# Main.net
KiCad netlist of a schematic drawn in Altium Designer
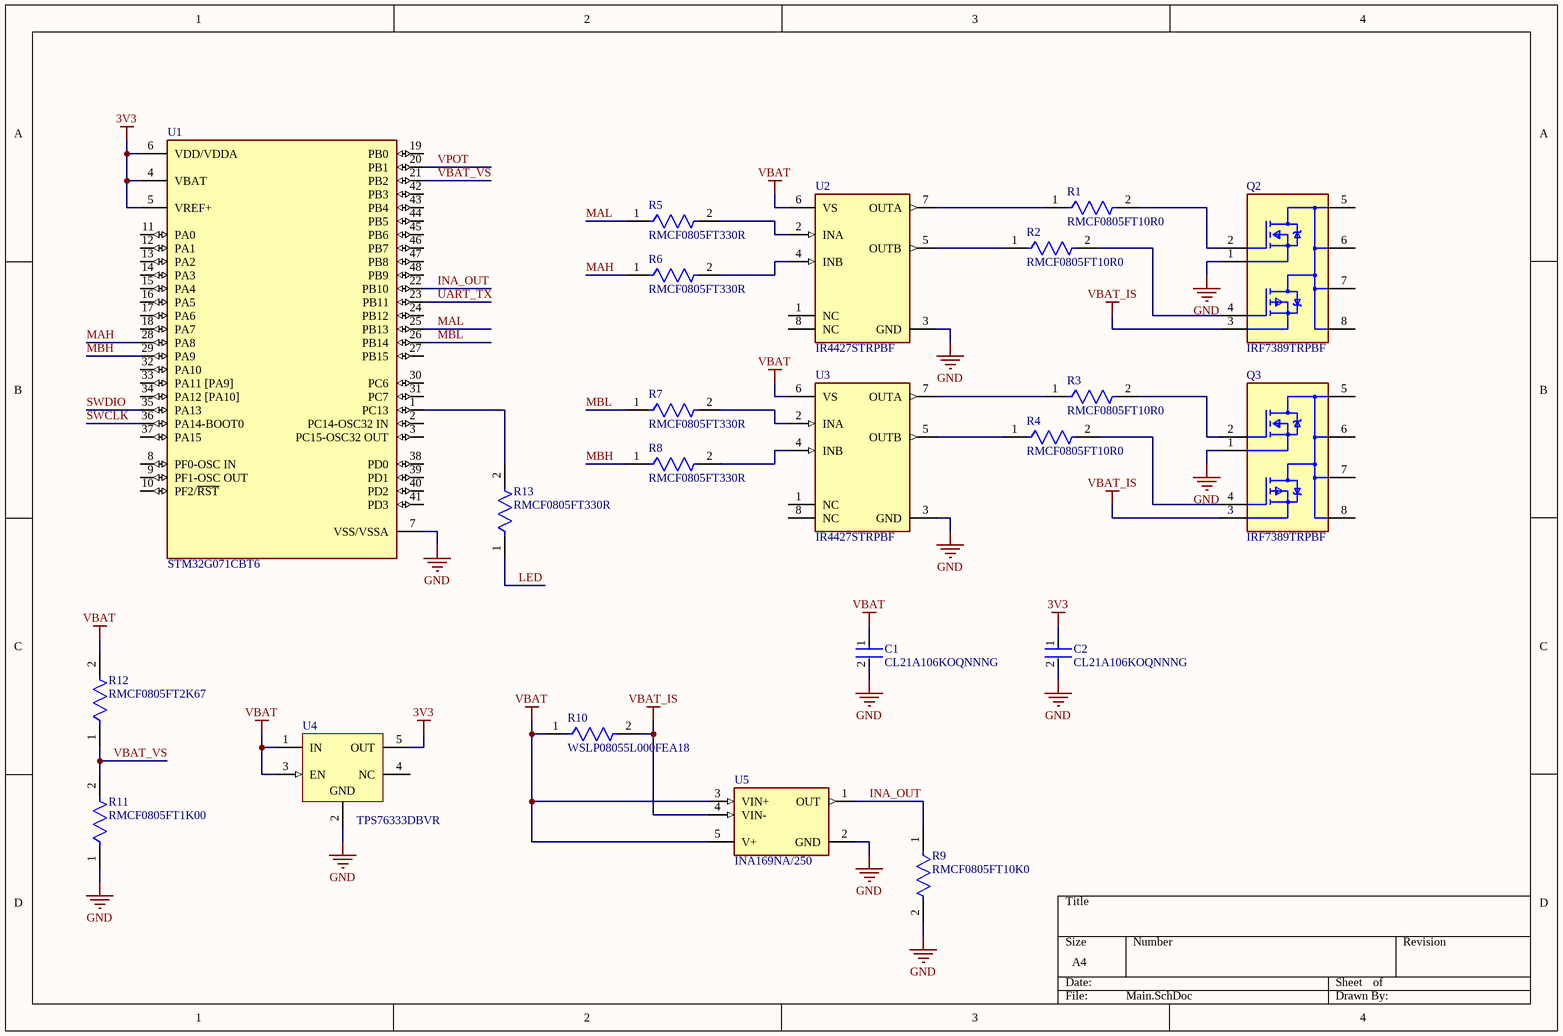
[diagram p0: Main.SchDoc]

(export (version "E")
  (design (tool "Eeschema 10.0.6"))
  (components
    (comp (ref "C1")
      (value "CL21A106KOQNNNG")
      (footprint "FP-CL21-IPC_C")
      (description "CL21 Series 0805 10uF 16V ±10% Tolerance X5R Multilayer Ceramic Chip Capacitor")
      (fields (field (name "TOLERANCE") "10%") (field (name "VOLTAGE") "16V"))
      (libsource (lib "Altium Content Vault") (part "b4654b650e69147ec39a6b967a45e02"))
    )
    (comp (ref "C2")
      (value "CL21A106KOQNNNG")
      (footprint "FP-CL21-IPC_C")
      (description "CL21 Series 0805 10uF 16V ±10% Tolerance X5R Multilayer Ceramic Chip Capacitor")
      (fields (field (name "TOLERANCE") "10%") (field (name "VOLTAGE") "16V"))
      (libsource (lib "Altium Content Vault") (part "b4654b650e69147ec39a6b967a45e02"))
    )
    (comp (ref "Q2")
      (value "IRF7389TRPBF")
      (footprint "FP-PG-DSO-8-MFG")
      (description "MOSFET N/P-CH 30V 8-SOIC")
      (libsource (lib "Altium Content Vault") (part "4824cb7145227b916d674334c6d10b0"))
    )
    (comp (ref "Q3")
      (value "IRF7389TRPBF")
      (footprint "FP-PG-DSO-8-MFG")
      (description "MOSFET N/P-CH 30V 8-SOIC")
      (libsource (lib "Altium Content Vault") (part "4824cb7145227b916d674334c6d10b0"))
    )
    (comp (ref "R1")
      (value "RMCF0805FT10R0")
      (footprint "FP-RMCF0805-IPC_C")
      (description "10Ω ±1% 0.125W 0805 Thick Film Chip Resistor AEC-Q200 compliant")
      (fields (field (name "TOLERANCE") "1%"))
      (libsource (lib "Altium Content Vault") (part "1029c3af85768c4190bb7ad29bc67b5"))
    )
    (comp (ref "R2")
      (value "RMCF0805FT10R0")
      (footprint "FP-RMCF0805-IPC_C")
      (description "10Ω ±1% 0.125W 0805 Thick Film Chip Resistor AEC-Q200 compliant")
      (fields (field (name "TOLERANCE") "1%"))
      (libsource (lib "Altium Content Vault") (part "1029c3af85768c4190bb7ad29bc67b5"))
    )
    (comp (ref "R3")
      (value "RMCF0805FT10R0")
      (footprint "FP-RMCF0805-IPC_C")
      (description "10Ω ±1% 0.125W 0805 Thick Film Chip Resistor AEC-Q200 compliant")
      (fields (field (name "TOLERANCE") "1%"))
      (libsource (lib "Altium Content Vault") (part "1029c3af85768c4190bb7ad29bc67b5"))
    )
    (comp (ref "R4")
      (value "RMCF0805FT10R0")
      (footprint "FP-RMCF0805-IPC_C")
      (description "10Ω ±1% 0.125W 0805 Thick Film Chip Resistor AEC-Q200 compliant")
      (fields (field (name "TOLERANCE") "1%"))
      (libsource (lib "Altium Content Vault") (part "1029c3af85768c4190bb7ad29bc67b5"))
    )
    (comp (ref "R5")
      (value "RMCF0805FT330R")
      (footprint "FP-RMCF0805-IPC_C")
      (description "330Ω ±1% 0.125W 0805 Thick Film Chip Resistor AEC-Q200 compliant")
      (fields (field (name "TOLERANCE") "1%"))
      (libsource (lib "Altium Content Vault") (part "1029c3af85768c4190bb7ad29bc67b5"))
    )
    (comp (ref "R6")
      (value "RMCF0805FT330R")
      (footprint "FP-RMCF0805-IPC_C")
      (description "330Ω ±1% 0.125W 0805 Thick Film Chip Resistor AEC-Q200 compliant")
      (fields (field (name "TOLERANCE") "1%"))
      (libsource (lib "Altium Content Vault") (part "1029c3af85768c4190bb7ad29bc67b5"))
    )
    (comp (ref "R7")
      (value "RMCF0805FT330R")
      (footprint "FP-RMCF0805-IPC_C")
      (description "330Ω ±1% 0.125W 0805 Thick Film Chip Resistor AEC-Q200 compliant")
      (fields (field (name "TOLERANCE") "1%"))
      (libsource (lib "Altium Content Vault") (part "1029c3af85768c4190bb7ad29bc67b5"))
    )
    (comp (ref "R8")
      (value "RMCF0805FT330R")
      (footprint "FP-RMCF0805-IPC_C")
      (description "330Ω ±1% 0.125W 0805 Thick Film Chip Resistor AEC-Q200 compliant")
      (fields (field (name "TOLERANCE") "1%"))
      (libsource (lib "Altium Content Vault") (part "1029c3af85768c4190bb7ad29bc67b5"))
    )
    (comp (ref "R9")
      (value "RMCF0805FT10K0")
      (footprint "FP-RMCF0805-IPC_C")
      (description "RES 10K OHM 1% 1/8W 0805")
      (fields (field (name "TOLERANCE") "1%"))
      (libsource (lib "Altium Content Vault") (part "1029c3af85768c4190bb7ad29bc67b5"))
    )
    (comp (ref "R10")
      (value "WSLP08055L000FEA18")
      (footprint "FP-WSLP0805-IPC_C")
      (description "RES 0.005 OHM 1% 1W 0805")
      (fields (field (name "TOLERANCE") "1%"))
      (libsource (lib "Altium Content Vault") (part "1029c3af85768c4190bb7ad29bc67b5"))
    )
    (comp (ref "R11")
      (value "RMCF0805FT1K00")
      (footprint "FP-RMCF0805-IPC_C")
      (description "1kΩ ±1% 0.125W 0805 Thick Film Chip Resistor AEC-Q200 compliant")
      (fields (field (name "TOLERANCE") "1%"))
      (libsource (lib "Altium Content Vault") (part "1029c3af85768c4190bb7ad29bc67b5"))
    )
    (comp (ref "R12")
      (value "RMCF0805FT2K67")
      (footprint "FP-RMCF0805-IPC_C")
      (description "2.67kΩ ±1% 0.125W 0805 Thick Film Chip Resistor AEC-Q200 compliant")
      (fields (field (name "TOLERANCE") "1%"))
      (libsource (lib "Altium Content Vault") (part "1029c3af85768c4190bb7ad29bc67b5"))
    )
    (comp (ref "R13")
      (value "RMCF0805FT330R")
      (footprint "FP-RMCF0805-IPC_C")
      (description "330Ω ±1% 0.125W 0805 Thick Film Chip Resistor AEC-Q200 compliant")
      (fields (field (name "TOLERANCE") "1%"))
      (libsource (lib "Altium Content Vault") (part "1029c3af85768c4190bb7ad29bc67b5"))
    )
    (comp (ref "U1")
      (value "STM32G071CBT6")
      (footprint "FP-LQFP48-5B-MFG")
      (description "IC MCU 32BIT 128KB FLASH 48LQFP")
      (fields
        (field (name "OCTOPART") "https://octopart.com/stm32g071cbt6-stmicroelectronics-96627027")
        (field (name "MANUFACTURER") "STMicroelectronics")
      )
      (libsource (lib "Altium Content Vault") (part "c9f63a35dbd129b66bfedb266152198"))
    )
    (comp (ref "U2")
      (value "IR4427STRPBF")
      (footprint "FP-PG-DSO-8-MFG")
      (description "IC DRIVER DUAL LOW SIDE 8SOIC")
      (fields (field (name "MANUFACTURER") "Infineon"))
      (libsource (lib "Altium Content Vault") (part "4c2f5f617ba2582f5a7cc1b9f55ba9e"))
    )
    (comp (ref "U3")
      (value "IR4427STRPBF")
      (footprint "FP-PG-DSO-8-MFG")
      (description "IC DRIVER DUAL LOW SIDE 8SOIC")
      (fields (field (name "MANUFACTURER") "Infineon"))
      (libsource (lib "Altium Content Vault") (part "4c2f5f617ba2582f5a7cc1b9f55ba9e"))
    )
    (comp (ref "U4")
      (value "TPS76333DBVR")
      (footprint "DBV0005A_N")
      (fields (field (name "MANUFACTURER") "Texas Instruments"))
      (libsource (lib "Altium Content Vault") (part "TI-TXX7XXXX-5"))
    )
    (comp (ref "U5")
      (value "INA169NA/250")
      (footprint "FP-DBV0005A-MFG")
      (description "IC CURRENT MONITOR 0.5% SOT23-5")
      (libsource (lib "Altium Content Vault") (part "e3922a93dcf1e78868155e6b684fbf7"))
    )
  )
  (nets
    (net (code "1") (name "/INA_OUT") (class "Default")
      (node (ref "R9") (pin "1") (pinfunction "1_1") (pintype "passive"))
      (node (ref "U1") (pin "22") (pinfunction "PB10_22") (pintype "bidirectional"))
      (node (ref "U5") (pin "1") (pinfunction "OUT_1") (pintype "output"))
    )
    (net (code "2") (name "/LED") (class "Default")
      (node (ref "R13") (pin "1") (pinfunction "1_1") (pintype "passive"))
    )
    (net (code "3") (name "/MAH") (class "Default")
      (node (ref "R6") (pin "1") (pinfunction "1_1") (pintype "passive"))
      (node (ref "U1") (pin "28") (pinfunction "PA8_28") (pintype "bidirectional"))
    )
    (net (code "4") (name "/MAL") (class "Default")
      (node (ref "R5") (pin "1") (pinfunction "1_1") (pintype "passive"))
      (node (ref "U1") (pin "25") (pinfunction "PB13_25") (pintype "bidirectional"))
    )
    (net (code "5") (name "/MBH") (class "Default")
      (node (ref "R8") (pin "1") (pinfunction "1_1") (pintype "passive"))
      (node (ref "U1") (pin "29") (pinfunction "PA9_29") (pintype "bidirectional"))
    )
    (net (code "6") (name "/MBL") (class "Default")
      (node (ref "R7") (pin "1") (pinfunction "1_1") (pintype "passive"))
      (node (ref "U1") (pin "26") (pinfunction "PB14_26") (pintype "bidirectional"))
    )
    (net (code "7") (name "/SWCLK") (class "Default")
      (node (ref "U1") (pin "36") (pinfunction "PA14-BOOT0_36") (pintype "bidirectional"))
    )
    (net (code "8") (name "/SWDIO") (class "Default")
      (node (ref "U1") (pin "35") (pinfunction "PA13_35") (pintype "bidirectional"))
    )
    (net (code "9") (name "/UART_TX") (class "Default")
      (node (ref "U1") (pin "23") (pinfunction "PB11_23") (pintype "bidirectional"))
    )
    (net (code "10") (name "/VBAT_VS") (class "Default")
      (node (ref "R11") (pin "2") (pinfunction "2_2") (pintype "passive"))
      (node (ref "R12") (pin "1") (pinfunction "1_1") (pintype "passive"))
      (node (ref "U1") (pin "21") (pinfunction "PB2_21") (pintype "bidirectional"))
    )
    (net (code "11") (name "/VPOT") (class "Default")
      (node (ref "U1") (pin "20") (pinfunction "PB1_20") (pintype "bidirectional"))
    )
    (net (code "12") (name "3V3") (class "Default")
      (node (ref "C2") (pin "1") (pinfunction "1_1") (pintype "passive"))
      (node (ref "U1") (pin "4") (pinfunction "VBAT_4") (pintype "power_in"))
      (node (ref "U1") (pin "5") (pinfunction "VREF+_5") (pintype "power_in"))
      (node (ref "U1") (pin "6") (pinfunction "VDD/VDDA_6") (pintype "power_in"))
      (node (ref "U4") (pin "5") (pinfunction "OUT_5") (pintype "power_in"))
    )
    (net (code "13") (name "GND") (class "Default")
      (node (ref "C1") (pin "2") (pinfunction "2_2") (pintype "passive"))
      (node (ref "C2") (pin "2") (pinfunction "2_2") (pintype "passive"))
      (node (ref "Q2") (pin "1") (pinfunction "S1_1") (pintype "passive"))
      (node (ref "Q3") (pin "1") (pinfunction "S1_1") (pintype "passive"))
      (node (ref "R11") (pin "1") (pinfunction "1_1") (pintype "passive"))
      (node (ref "R9") (pin "2") (pinfunction "2_2") (pintype "passive"))
      (node (ref "U1") (pin "7") (pinfunction "VSS/VSSA_7") (pintype "power_in"))
      (node (ref "U2") (pin "3") (pinfunction "GND_3") (pintype "power_in"))
      (node (ref "U3") (pin "3") (pinfunction "GND_3") (pintype "power_in"))
      (node (ref "U4") (pin "2") (pinfunction "GND_2") (pintype "power_in"))
      (node (ref "U5") (pin "2") (pinfunction "GND_2") (pintype "power_in"))
    )
    (net (code "14") (name "Net-(Q2-G1)") (class "Default")
      (node (ref "Q2") (pin "2") (pinfunction "G1_2") (pintype "passive"))
      (node (ref "R1") (pin "2") (pinfunction "2_2") (pintype "passive"))
    )
    (net (code "15") (name "Net-(Q2-G2)") (class "Default")
      (node (ref "Q2") (pin "4") (pinfunction "G2_4") (pintype "passive"))
      (node (ref "R2") (pin "2") (pinfunction "2_2") (pintype "passive"))
    )
    (net (code "16") (name "Net-(Q3-G1)") (class "Default")
      (node (ref "Q3") (pin "2") (pinfunction "G1_2") (pintype "passive"))
      (node (ref "R3") (pin "2") (pinfunction "2_2") (pintype "passive"))
    )
    (net (code "17") (name "Net-(Q3-G2)") (class "Default")
      (node (ref "Q3") (pin "4") (pinfunction "G2_4") (pintype "passive"))
      (node (ref "R4") (pin "2") (pinfunction "2_2") (pintype "passive"))
    )
    (net (code "18") (name "Net-(U1-PC13)") (class "Default")
      (node (ref "R13") (pin "2") (pinfunction "2_2") (pintype "passive"))
      (node (ref "U1") (pin "1") (pinfunction "PC13_1") (pintype "bidirectional"))
    )
    (net (code "19") (name "Net-(U2-INA)") (class "Default")
      (node (ref "R5") (pin "2") (pinfunction "2_2") (pintype "passive"))
      (node (ref "U2") (pin "2") (pinfunction "INA_2") (pintype "input"))
    )
    (net (code "20") (name "Net-(U2-INB)") (class "Default")
      (node (ref "R6") (pin "2") (pinfunction "2_2") (pintype "passive"))
      (node (ref "U2") (pin "4") (pinfunction "INB_4") (pintype "input"))
    )
    (net (code "21") (name "Net-(U2-OUTA)") (class "Default")
      (node (ref "R1") (pin "1") (pinfunction "1_1") (pintype "passive"))
      (node (ref "U2") (pin "7") (pinfunction "OUTA_7") (pintype "output"))
    )
    (net (code "22") (name "Net-(U2-OUTB)") (class "Default")
      (node (ref "R2") (pin "1") (pinfunction "1_1") (pintype "passive"))
      (node (ref "U2") (pin "5") (pinfunction "OUTB_5") (pintype "output"))
    )
    (net (code "23") (name "Net-(U3-INA)") (class "Default")
      (node (ref "R7") (pin "2") (pinfunction "2_2") (pintype "passive"))
      (node (ref "U3") (pin "2") (pinfunction "INA_2") (pintype "input"))
    )
    (net (code "24") (name "Net-(U3-INB)") (class "Default")
      (node (ref "R8") (pin "2") (pinfunction "2_2") (pintype "passive"))
      (node (ref "U3") (pin "4") (pinfunction "INB_4") (pintype "input"))
    )
    (net (code "25") (name "Net-(U3-OUTA)") (class "Default")
      (node (ref "R3") (pin "1") (pinfunction "1_1") (pintype "passive"))
      (node (ref "U3") (pin "7") (pinfunction "OUTA_7") (pintype "output"))
    )
    (net (code "26") (name "Net-(U3-OUTB)") (class "Default")
      (node (ref "R4") (pin "1") (pinfunction "1_1") (pintype "passive"))
      (node (ref "U3") (pin "5") (pinfunction "OUTB_5") (pintype "output"))
    )
    (net (code "27") (name "VBAT") (class "Default")
      (node (ref "C1") (pin "1") (pinfunction "1_1") (pintype "passive"))
      (node (ref "R10") (pin "1") (pinfunction "1_1") (pintype "passive"))
      (node (ref "R12") (pin "2") (pinfunction "2_2") (pintype "passive"))
      (node (ref "U2") (pin "6") (pinfunction "VS_6") (pintype "power_in"))
      (node (ref "U3") (pin "6") (pinfunction "VS_6") (pintype "power_in"))
      (node (ref "U4") (pin "1") (pinfunction "IN_1") (pintype "power_in"))
      (node (ref "U4") (pin "3") (pinfunction "EN_3") (pintype "input"))
      (node (ref "U5") (pin "3") (pinfunction "VIN+_3") (pintype "input"))
      (node (ref "U5") (pin "5") (pinfunction "V+_5") (pintype "power_in"))
    )
    (net (code "28") (name "VBAT_IS") (class "Default")
      (node (ref "Q2") (pin "3") (pinfunction "S2_3") (pintype "passive"))
      (node (ref "Q3") (pin "3") (pinfunction "S2_3") (pintype "passive"))
      (node (ref "R10") (pin "2") (pinfunction "2_2") (pintype "passive"))
      (node (ref "U5") (pin "4") (pinfunction "VIN-_4") (pintype "input"))
    )
    (net (code "29") (name "unconnected-(Q2-D-Pad5)") (class "Default")
      (node (ref "Q2") (pin "5") (pinfunction "D_5") (pintype "passive"))
    )
    (net (code "30") (name "unconnected-(Q2-D-Pad6)") (class "Default")
      (node (ref "Q2") (pin "6") (pinfunction "D_6") (pintype "passive"))
    )
    (net (code "31") (name "unconnected-(Q2-D-Pad7)") (class "Default")
      (node (ref "Q2") (pin "7") (pinfunction "D_7") (pintype "passive"))
    )
    (net (code "32") (name "unconnected-(Q2-D-Pad8)") (class "Default")
      (node (ref "Q2") (pin "8") (pinfunction "D_8") (pintype "passive"))
    )
    (net (code "33") (name "unconnected-(Q3-D-Pad5)") (class "Default")
      (node (ref "Q3") (pin "5") (pinfunction "D_5") (pintype "passive"))
    )
    (net (code "34") (name "unconnected-(Q3-D-Pad6)") (class "Default")
      (node (ref "Q3") (pin "6") (pinfunction "D_6") (pintype "passive"))
    )
    (net (code "35") (name "unconnected-(Q3-D-Pad7)") (class "Default")
      (node (ref "Q3") (pin "7") (pinfunction "D_7") (pintype "passive"))
    )
    (net (code "36") (name "unconnected-(Q3-D-Pad8)") (class "Default")
      (node (ref "Q3") (pin "8") (pinfunction "D_8") (pintype "passive"))
    )
    (net (code "37") (name "unconnected-(U1-PA0-Pad11)") (class "Default")
      (node (ref "U1") (pin "11") (pinfunction "PA0_11") (pintype "bidirectional"))
    )
    (net (code "38") (name "unconnected-(U1-PA1-Pad12)") (class "Default")
      (node (ref "U1") (pin "12") (pinfunction "PA1_12") (pintype "bidirectional"))
    )
    (net (code "39") (name "unconnected-(U1-PA2-Pad13)") (class "Default")
      (node (ref "U1") (pin "13") (pinfunction "PA2_13") (pintype "bidirectional"))
    )
    (net (code "40") (name "unconnected-(U1-PA3-Pad14)") (class "Default")
      (node (ref "U1") (pin "14") (pinfunction "PA3_14") (pintype "bidirectional"))
    )
    (net (code "41") (name "unconnected-(U1-PA4-Pad15)") (class "Default")
      (node (ref "U1") (pin "15") (pinfunction "PA4_15") (pintype "bidirectional"))
    )
    (net (code "42") (name "unconnected-(U1-PA5-Pad16)") (class "Default")
      (node (ref "U1") (pin "16") (pinfunction "PA5_16") (pintype "bidirectional"))
    )
    (net (code "43") (name "unconnected-(U1-PA6-Pad17)") (class "Default")
      (node (ref "U1") (pin "17") (pinfunction "PA6_17") (pintype "bidirectional"))
    )
    (net (code "44") (name "unconnected-(U1-PA7-Pad18)") (class "Default")
      (node (ref "U1") (pin "18") (pinfunction "PA7_18") (pintype "bidirectional"))
    )
    (net (code "45") (name "unconnected-(U1-PA10-Pad32)") (class "Default")
      (node (ref "U1") (pin "32") (pinfunction "PA10_32") (pintype "bidirectional"))
    )
    (net (code "46") (name "unconnected-(U1-PA11_[PA9]-Pad33)") (class "Default")
      (node (ref "U1") (pin "33") (pinfunction "PA11_[PA9]_33") (pintype "bidirectional"))
    )
    (net (code "47") (name "unconnected-(U1-PA12_[PA10]-Pad34)") (class "Default")
      (node (ref "U1") (pin "34") (pinfunction "PA12_[PA10]_34") (pintype "bidirectional"))
    )
    (net (code "48") (name "unconnected-(U1-PA15-Pad37)") (class "Default")
      (node (ref "U1") (pin "37") (pinfunction "PA15_37") (pintype "bidirectional"))
    )
    (net (code "49") (name "unconnected-(U1-PB0-Pad19)") (class "Default")
      (node (ref "U1") (pin "19") (pinfunction "PB0_19") (pintype "bidirectional"))
    )
    (net (code "50") (name "unconnected-(U1-PB3-Pad42)") (class "Default")
      (node (ref "U1") (pin "42") (pinfunction "PB3_42") (pintype "bidirectional"))
    )
    (net (code "51") (name "unconnected-(U1-PB4-Pad43)") (class "Default")
      (node (ref "U1") (pin "43") (pinfunction "PB4_43") (pintype "bidirectional"))
    )
    (net (code "52") (name "unconnected-(U1-PB5-Pad44)") (class "Default")
      (node (ref "U1") (pin "44") (pinfunction "PB5_44") (pintype "bidirectional"))
    )
    (net (code "53") (name "unconnected-(U1-PB6-Pad45)") (class "Default")
      (node (ref "U1") (pin "45") (pinfunction "PB6_45") (pintype "bidirectional"))
    )
    (net (code "54") (name "unconnected-(U1-PB7-Pad46)") (class "Default")
      (node (ref "U1") (pin "46") (pinfunction "PB7_46") (pintype "bidirectional"))
    )
    (net (code "55") (name "unconnected-(U1-PB8-Pad47)") (class "Default")
      (node (ref "U1") (pin "47") (pinfunction "PB8_47") (pintype "bidirectional"))
    )
    (net (code "56") (name "unconnected-(U1-PB9-Pad48)") (class "Default")
      (node (ref "U1") (pin "48") (pinfunction "PB9_48") (pintype "bidirectional"))
    )
    (net (code "57") (name "unconnected-(U1-PB12-Pad24)") (class "Default")
      (node (ref "U1") (pin "24") (pinfunction "PB12_24") (pintype "bidirectional"))
    )
    (net (code "58") (name "unconnected-(U1-PB15-Pad27)") (class "Default")
      (node (ref "U1") (pin "27") (pinfunction "PB15_27") (pintype "bidirectional"))
    )
    (net (code "59") (name "unconnected-(U1-PC6-Pad30)") (class "Default")
      (node (ref "U1") (pin "30") (pinfunction "PC6_30") (pintype "bidirectional"))
    )
    (net (code "60") (name "unconnected-(U1-PC7-Pad31)") (class "Default")
      (node (ref "U1") (pin "31") (pinfunction "PC7_31") (pintype "bidirectional"))
    )
    (net (code "61") (name "unconnected-(U1-PC14-OSC32_IN-Pad2)") (class "Default")
      (node (ref "U1") (pin "2") (pinfunction "PC14-OSC32_IN_2") (pintype "bidirectional"))
    )
    (net (code "62") (name "unconnected-(U1-PC15-OSC32_OUT-Pad3)") (class "Default")
      (node (ref "U1") (pin "3") (pinfunction "PC15-OSC32_OUT_3") (pintype "bidirectional"))
    )
    (net (code "63") (name "unconnected-(U1-PD0-Pad38)") (class "Default")
      (node (ref "U1") (pin "38") (pinfunction "PD0_38") (pintype "bidirectional"))
    )
    (net (code "64") (name "unconnected-(U1-PD1-Pad39)") (class "Default")
      (node (ref "U1") (pin "39") (pinfunction "PD1_39") (pintype "bidirectional"))
    )
    (net (code "65") (name "unconnected-(U1-PD2-Pad40)") (class "Default")
      (node (ref "U1") (pin "40") (pinfunction "PD2_40") (pintype "bidirectional"))
    )
    (net (code "66") (name "unconnected-(U1-PD3-Pad41)") (class "Default")
      (node (ref "U1") (pin "41") (pinfunction "PD3_41") (pintype "bidirectional"))
    )
    (net (code "67") (name "unconnected-(U1-PF0-OSC_IN-Pad8)") (class "Default")
      (node (ref "U1") (pin "8") (pinfunction "PF0-OSC_IN_8") (pintype "bidirectional"))
    )
    (net (code "68") (name "unconnected-(U1-PF1-OSC_OUT-Pad9)") (class "Default")
      (node (ref "U1") (pin "9") (pinfunction "PF1-OSC_OUT_9") (pintype "bidirectional"))
    )
    (net (code "69") (name "unconnected-(U1-PF2{slash}~{RST}-Pad10)") (class "Default")
      (node (ref "U1") (pin "10") (pinfunction "PF2/~{RST}_10") (pintype "bidirectional"))
    )
    (net (code "70") (name "unconnected-(U2-NC-Pad1)") (class "Default")
      (node (ref "U2") (pin "1") (pinfunction "NC_1") (pintype "passive"))
    )
    (net (code "71") (name "unconnected-(U2-NC-Pad8)") (class "Default")
      (node (ref "U2") (pin "8") (pinfunction "NC_8") (pintype "passive"))
    )
    (net (code "72") (name "unconnected-(U3-NC-Pad1)") (class "Default")
      (node (ref "U3") (pin "1") (pinfunction "NC_1") (pintype "passive"))
    )
    (net (code "73") (name "unconnected-(U3-NC-Pad8)") (class "Default")
      (node (ref "U3") (pin "8") (pinfunction "NC_8") (pintype "passive"))
    )
    (net (code "74") (name "unconnected-(U4-NC-Pad4)") (class "Default")
      (node (ref "U4") (pin "4") (pinfunction "NC_4") (pintype "passive"))
    )
  )
)
